# Sheet1.net
KiCad netlist of a schematic drawn in Altium Designer
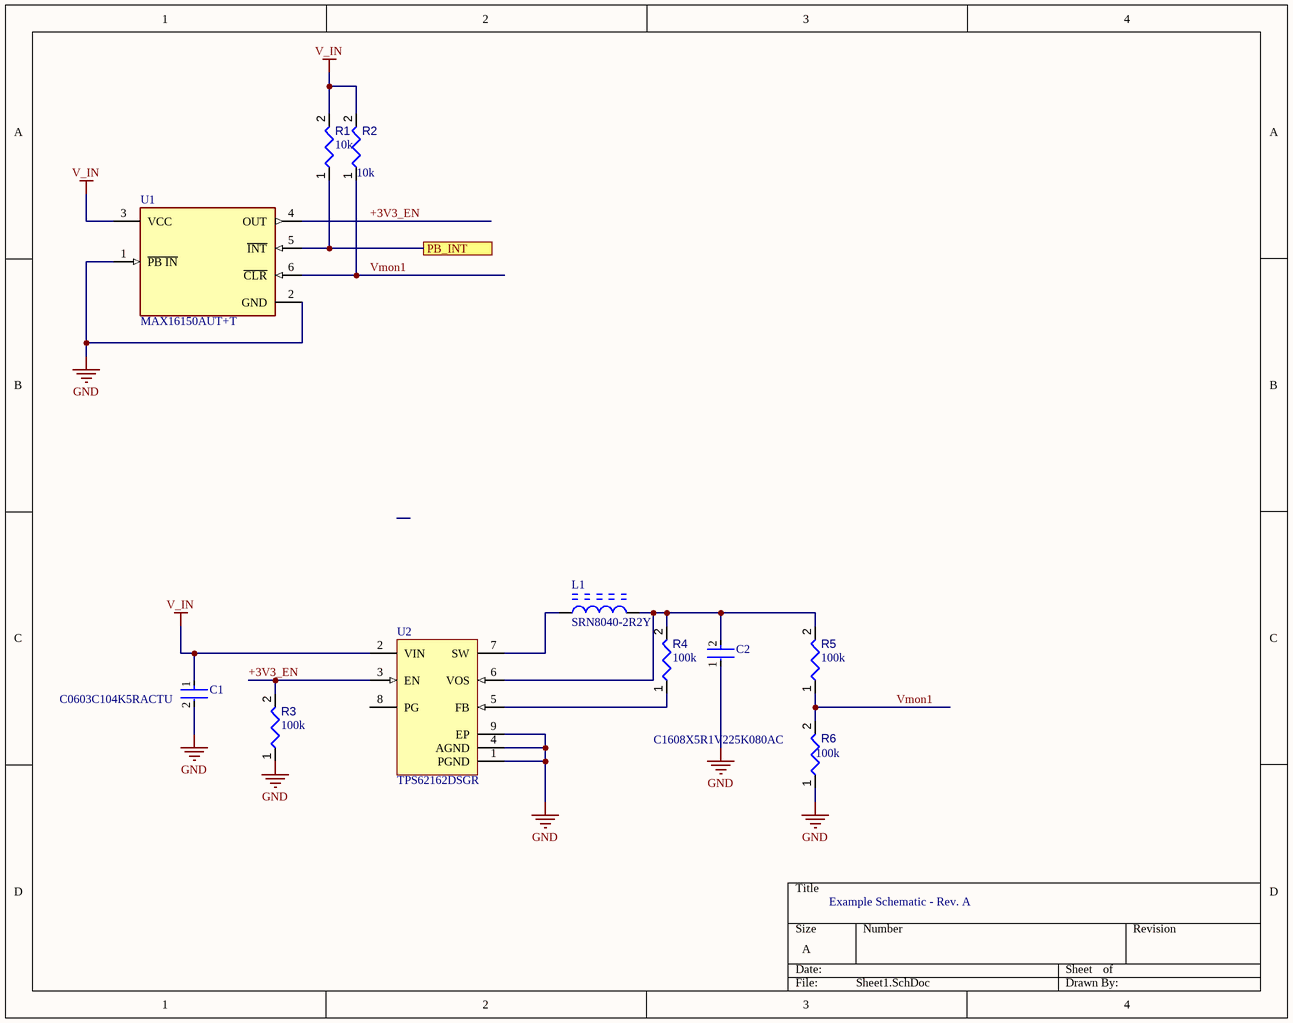
[diagram p0: Sheet1.SchDoc]

(export (version "E")
  (design (tool "Eeschema 10.0.6"))
  (components
    (comp (ref "C1")
      (value "C0603C104K5RACTU")
      (footprint "FP-C0603C-CF-MFG")
      (description "C0603 0.10 μF X7R 30ppm/°C 10.00% 50 V")
      (fields (field (name "TOLERANCE") "0.1"))
      (libsource (lib "Altium Content Vault") (part "b4654b650e69147ec39a6b967a45e02"))
    )
    (comp (ref "C2")
      (value "C1608X5R1V225K080AC")
      (footprint "FP-C1608-080-0_1-MFG")
      (description "Multilayer Ceramic Capacitors 2.2μF ±10% 35V X5R SMD 0603")
      (fields (field (name "TOLERANCE") "10%") (field (name "VOLTAGE") "35V"))
      (libsource (lib "Altium Content Vault") (part "236180d848d6139a670b325ea6854c9"))
    )
    (comp (ref "L1")
      (value "SRN8040-2R2Y")
      (footprint "BOUR-SRN8040_V")
      (fields (field (name "MANUFACTURER") "Bourns") (field (name "TOLERANCE") "±30%"))
      (libsource (lib "Altium Content Vault") (part "IND-FERR-2"))
    )
    (comp (ref "R1")
      (value "10k")
      (footprint "RESC1005X40X25ML05T05")
      (description "Chip Resistor, 10 KOhm, +/- 1%, 0.1 W, -55 to 155 degC, 0402 (1005 Metric)")
      (fields (field (name "TOLERANCE") "1%") (field (name "POWER") "100mW"))
      (libsource (lib "joshua_workspace") (part "RES-2"))
    )
    (comp (ref "R2")
      (value "10k")
      (footprint "RESC1005X40X25ML05T05")
      (description "Chip Resistor, 10 KOhm, +/- 1%, 0.1 W, -55 to 155 degC, 0402 (1005 Metric)")
      (fields (field (name "TOLERANCE") "1%") (field (name "POWER") "100mW"))
      (libsource (lib "joshua_workspace") (part "RES-2"))
    )
    (comp (ref "R3")
      (value "100k")
      (footprint "RESC1608X55X25ML10T15")
      (description "Chip Resistor, 100 KOhm, +/- 1%, 0.1 W, -55 to 155 degC, 0603 (1608 Metric)")
      (fields (field (name "TOLERANCE") "1%") (field (name "POWER") "100mW"))
      (libsource (lib "joshua_workspace") (part "RES-2"))
    )
    (comp (ref "R4")
      (value "100k")
      (footprint "RESC1608X55X25ML10T15")
      (description "Chip Resistor, 100 KOhm, +/- 1%, 0.1 W, -55 to 155 degC, 0603 (1608 Metric)")
      (fields (field (name "TOLERANCE") "1%") (field (name "POWER") "100mW"))
      (libsource (lib "joshua_workspace") (part "RES-2"))
    )
    (comp (ref "R5")
      (value "100k")
      (footprint "RESC1608X55X25ML10T15")
      (description "Chip Resistor, 100 KOhm, +/- 1%, 0.1 W, -55 to 155 degC, 0603 (1608 Metric)")
      (fields (field (name "TOLERANCE") "1%") (field (name "POWER") "100mW"))
      (libsource (lib "joshua_workspace") (part "RES-2"))
    )
    (comp (ref "R6")
      (value "100k")
      (footprint "RESC1608X55X25ML10T15")
      (description "Chip Resistor, 100 KOhm, +/- 1%, 0.1 W, -55 to 155 degC, 0603 (1608 Metric)")
      (fields (field (name "TOLERANCE") "1%") (field (name "POWER") "100mW"))
      (libsource (lib "joshua_workspace") (part "RES-2"))
    )
    (comp (ref "U1")
      (value "MAX16150AUT+T")
      (footprint "FP-U6-1-MFG")
      (description "IC SUPERVISOR 1 CHANNEL SOT23-6")
      (libsource (lib "Altium Content Vault") (part "36a392858d03d148bb8ce7f45f4b5f9"))
    )
    (comp (ref "U2")
      (value "TPS62162DSGR")
      (footprint "DSG0008A_V")
      (fields (field (name "MANUFACTURER") "Texas Instruments"))
      (libsource (lib "Altium Content Vault") (part "TI-TPS62162DSG8-1600X900TP"))
    )
  )
  (nets
    (net (code "1") (name "/+3V3_EN") (class "Default")
      (node (ref "R3") (pin "2") (pinfunction "2_2") (pintype "passive"))
      (node (ref "U1") (pin "4") (pinfunction "OUT_4") (pintype "output"))
      (node (ref "U2") (pin "3") (pinfunction "EN_3") (pintype "input"))
    )
    (net (code "2") (name "/PB_INT") (class "Default")
      (node (ref "R1") (pin "1") (pinfunction "1_1") (pintype "passive"))
      (node (ref "U1") (pin "5") (pinfunction "~{INT}_5") (pintype "input"))
    )
    (net (code "3") (name "/Vmon1") (class "Default")
      (node (ref "R2") (pin "1") (pinfunction "1_1") (pintype "passive"))
      (node (ref "R5") (pin "1") (pinfunction "1_1") (pintype "passive"))
      (node (ref "R6") (pin "2") (pinfunction "2_2") (pintype "passive"))
      (node (ref "U1") (pin "6") (pinfunction "~{CLR}_6") (pintype "input"))
    )
    (net (code "4") (name "GND") (class "Default")
      (node (ref "C1") (pin "2") (pinfunction "2_2") (pintype "passive"))
      (node (ref "C2") (pin "1") (pinfunction "1_1") (pintype "passive"))
      (node (ref "R3") (pin "1") (pinfunction "1_1") (pintype "passive"))
      (node (ref "R6") (pin "1") (pinfunction "1_1") (pintype "passive"))
      (node (ref "U1") (pin "1") (pinfunction "~{PB_IN}_1") (pintype "input"))
      (node (ref "U1") (pin "2") (pinfunction "GND_2") (pintype "power_in"))
      (node (ref "U2") (pin "1") (pinfunction "PGND_1") (pintype "power_in"))
      (node (ref "U2") (pin "4") (pinfunction "AGND_4") (pintype "power_in"))
      (node (ref "U2") (pin "9") (pinfunction "EP_9") (pintype "power_in"))
    )
    (net (code "5") (name "Net-(U2-FB)") (class "Default")
      (node (ref "R4") (pin "1") (pinfunction "1_1") (pintype "passive"))
      (node (ref "U2") (pin "5") (pinfunction "FB_5") (pintype "input"))
    )
    (net (code "6") (name "Net-(U2-SW)") (class "Default")
      (node (ref "L1") (pin "1") (pinfunction "1_1") (pintype "passive"))
      (node (ref "U2") (pin "7") (pinfunction "SW_7") (pintype "power_in"))
    )
    (net (code "7") (name "Net-(U2-VOS)") (class "Default")
      (node (ref "C2") (pin "2") (pinfunction "2_2") (pintype "passive"))
      (node (ref "L1") (pin "2") (pinfunction "2_2") (pintype "passive"))
      (node (ref "R4") (pin "2") (pinfunction "2_2") (pintype "passive"))
      (node (ref "R5") (pin "2") (pinfunction "2_2") (pintype "passive"))
      (node (ref "U2") (pin "6") (pinfunction "VOS_6") (pintype "input"))
    )
    (net (code "8") (name "V_IN") (class "Default")
      (node (ref "C1") (pin "1") (pinfunction "1_1") (pintype "passive"))
      (node (ref "R1") (pin "2") (pinfunction "2_2") (pintype "passive"))
      (node (ref "R2") (pin "2") (pinfunction "2_2") (pintype "passive"))
      (node (ref "U1") (pin "3") (pinfunction "VCC_3") (pintype "power_in"))
      (node (ref "U2") (pin "2") (pinfunction "VIN_2") (pintype "power_in"))
    )
    (net (code "9") (name "unconnected-(U2-PG-Pad8)") (class "Default")
      (node (ref "U2") (pin "8") (pinfunction "PG_8") (pintype "tri_state"))
    )
  )
)
